# 51.net
KiCad netlist of a schematic drawn in Altium Designer
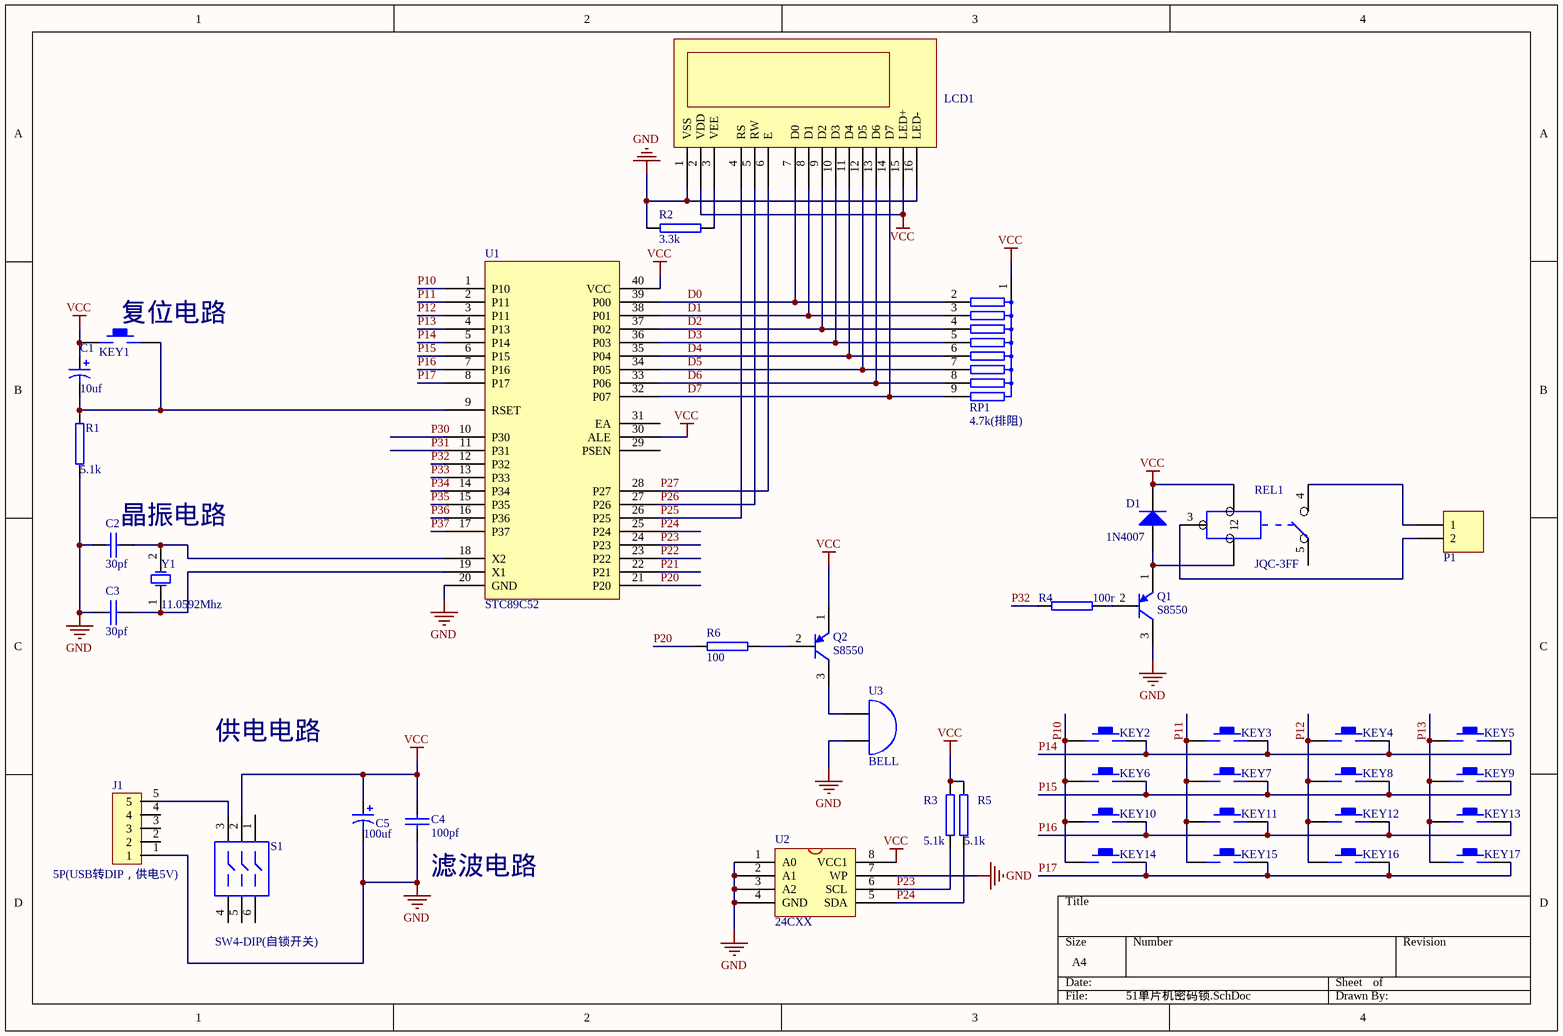
[diagram p0: 51单片机密码锁.SchDoc]

(export (version "E")
  (design (tool "Eeschema 10.0.6"))
  (components
    (comp (ref "C1")
      (value "10uf")
      (footprint "RB.2/.4")
      (description "Polarized Capacitor (Axial)")
      (fields (field (name "VAULE") "10uf") (field (name "PUBLISHER") "Altium Limited"))
      (libsource (lib "my") (part "CAPPOL"))
    )
    (comp (ref "C2") (value "30pf") (footprint "C0.2") (libsource (lib "my") (part "CAP")))
    (comp (ref "C3") (value "30pf") (footprint "C0.2") (libsource (lib "my") (part "CAP")))
    (comp (ref "C4") (value "100pf") (footprint "C0.2") (libsource (lib "my") (part "CAP")))
    (comp (ref "C5")
      (value "100uf")
      (footprint "RB.2/.4")
      (description "Polarized Capacitor (Axial)")
      (fields (field (name "PUBLISHER") "Altium Limited"))
      (libsource (lib "my") (part "CAPPOL"))
    )
    (comp (ref "D1")
      (value "Diode")
      (footprint "DIODE-0.4")
      (description "二极管")
      (fields (field (name "TYPE") "1N4007") (field (name "PUBLISHER") "Altium Limited"))
      (libsource (lib "my封装") (part "Diode"))
    )
    (comp (ref "J1") (value "5P(USB转DIP，供电5V)") (footprint "5P") (libsource (lib "my封装") (part "5P")))
    (comp (ref "KEY1") (value "KEY") (footprint "KEY") (libsource (lib "my电子集成封装库") (part "KEY")))
    (comp (ref "KEY2")
      (value "KEY")
      (footprint "KEY")
      (description "按键")
      (libsource (lib "my封装") (part "KEY"))
    )
    (comp (ref "KEY3")
      (value "KEY")
      (footprint "KEY")
      (description "按键")
      (libsource (lib "my封装") (part "KEY"))
    )
    (comp (ref "KEY4")
      (value "KEY")
      (footprint "KEY")
      (description "按键")
      (libsource (lib "my封装") (part "KEY"))
    )
    (comp (ref "KEY5")
      (value "KEY")
      (footprint "KEY")
      (description "按键")
      (libsource (lib "my封装") (part "KEY"))
    )
    (comp (ref "KEY6")
      (value "KEY")
      (footprint "KEY")
      (description "按键")
      (libsource (lib "my封装") (part "KEY"))
    )
    (comp (ref "KEY7")
      (value "KEY")
      (footprint "KEY")
      (description "按键")
      (libsource (lib "my封装") (part "KEY"))
    )
    (comp (ref "KEY8")
      (value "KEY")
      (footprint "KEY")
      (description "按键")
      (libsource (lib "my封装") (part "KEY"))
    )
    (comp (ref "KEY9")
      (value "KEY")
      (footprint "KEY")
      (description "按键")
      (libsource (lib "my封装") (part "KEY"))
    )
    (comp (ref "KEY10")
      (value "KEY")
      (footprint "KEY")
      (description "按键")
      (libsource (lib "my封装") (part "KEY"))
    )
    (comp (ref "KEY11")
      (value "KEY")
      (footprint "KEY")
      (description "按键")
      (libsource (lib "my封装") (part "KEY"))
    )
    (comp (ref "KEY12")
      (value "KEY")
      (footprint "KEY")
      (description "按键")
      (libsource (lib "my封装") (part "KEY"))
    )
    (comp (ref "KEY13")
      (value "KEY")
      (footprint "KEY")
      (description "按键")
      (libsource (lib "my封装") (part "KEY"))
    )
    (comp (ref "KEY14")
      (value "KEY")
      (footprint "KEY")
      (description "按键")
      (libsource (lib "my封装") (part "KEY"))
    )
    (comp (ref "KEY15")
      (value "KEY")
      (footprint "KEY")
      (description "按键")
      (libsource (lib "my封装") (part "KEY"))
    )
    (comp (ref "KEY16")
      (value "KEY")
      (footprint "KEY")
      (description "按键")
      (libsource (lib "my封装") (part "KEY"))
    )
    (comp (ref "KEY17")
      (value "KEY")
      (footprint "KEY")
      (description "按键")
      (libsource (lib "my封装") (part "KEY"))
    )
    (comp (ref "LCD1") (value "LCD1602") (footprint "SIP16") (libsource (lib "my封装") (part "LCD1602")))
    (comp (ref "P1")
      (value "Header 2")
      (footprint "HDR2X1_A")
      (description "接插件")
      (fields (field (name "PUBLISHER") "Altium Limited"))
      (libsource (lib "my封装") (part "Header 2"))
    )
    (comp (ref "Q1")
      (value "S8550")
      (footprint "TO-92A")
      (description "PNP三极管")
      (fields (field (name "PUBLISHER") "Altium Limited"))
      (libsource (lib "my封装") (part "S8550"))
    )
    (comp (ref "Q2")
      (value "S8550")
      (footprint "TO-92A")
      (description "PNP三极管")
      (fields (field (name "PUBLISHER") "Altium Limited"))
      (libsource (lib "my封装") (part "S8550"))
    )
    (comp (ref "R1") (value "5.1k") (footprint "AXIAL0.4") (libsource (lib "my") (part "RES")))
    (comp (ref "R2")
      (value "3.3k")
      (footprint "AXIAL0.4")
      (description "电阻")
      (libsource (lib "my封装") (part "RES"))
    )
    (comp (ref "R3") (value "5.1k") (footprint "AXIAL0.4") (libsource (lib "my") (part "RES")))
    (comp (ref "R4") (value "100r") (footprint "AXIAL0.4") (libsource (lib "my") (part "RES")))
    (comp (ref "R5") (value "5.1k") (footprint "AXIAL0.4") (libsource (lib "my") (part "RES")))
    (comp (ref "R6")
      (value "100")
      (footprint "AXIAL0.4")
      (description "电阻")
      (libsource (lib "my封装") (part "RES"))
    )
    (comp (ref "REL1")
      (value "JQC-3FF")
      (footprint "JQC-3FF-1")
      (description "继电器")
      (libsource (lib "my封装") (part "REL-5"))
    )
    (comp (ref "RP1") (value "4.7k(排阻)") (footprint "SIP9") (libsource (lib "my电子集成封装库") (part "RP8")))
    (comp (ref "S1") (value "SW4-DIP(自锁开关)") (footprint "SW6") (libsource (lib "my封装") (part "SW4-DIP")))
    (comp (ref "U1") (value "STC89C52") (footprint "DIP40") (libsource (lib "my") (part "STC89C52")))
    (comp (ref "U2")
      (value "24CXX")
      (footprint "DIP8")
      (description "存储芯片")
      (libsource (lib "my封装") (part "24CXX"))
    )
    (comp (ref "U3")
      (value "BELL")
      (footprint "BELL")
      (description "蜂鸣器")
      (libsource (lib "my封装") (part "BELL"))
    )
    (comp (ref "Y1")
      (value "11.0592Mhz")
      (footprint "CRYSTAL")
      (description "Crystal Oscillator")
      (fields (field (name "PUBLISHER") "*"))
      (libsource (lib "CRYSTALS") (part "XTAL"))
    )
  )
  (nets
    (net (code "1") (name "/D0") (class "Default")
      (node (ref "LCD1") (pin "7") (pinfunction "D0_7") (pintype "passive"))
      (node (ref "RP1") (pin "2") (pintype "passive"))
      (node (ref "U1") (pin "39") (pinfunction "P00_39") (pintype "passive"))
    )
    (net (code "2") (name "/D1") (class "Default")
      (node (ref "LCD1") (pin "8") (pinfunction "D1_8") (pintype "passive"))
      (node (ref "RP1") (pin "3") (pintype "passive"))
      (node (ref "U1") (pin "38") (pinfunction "P01_38") (pintype "passive"))
    )
    (net (code "3") (name "/D2") (class "Default")
      (node (ref "LCD1") (pin "9") (pinfunction "D2_9") (pintype "passive"))
      (node (ref "RP1") (pin "4") (pintype "passive"))
      (node (ref "U1") (pin "37") (pinfunction "P02_37") (pintype "passive"))
    )
    (net (code "4") (name "/D3") (class "Default")
      (node (ref "LCD1") (pin "10") (pinfunction "D3_10") (pintype "passive"))
      (node (ref "RP1") (pin "5") (pintype "passive"))
      (node (ref "U1") (pin "36") (pinfunction "P03_36") (pintype "passive"))
    )
    (net (code "5") (name "/D4") (class "Default")
      (node (ref "LCD1") (pin "11") (pinfunction "D4_11") (pintype "passive"))
      (node (ref "RP1") (pin "6") (pintype "passive"))
      (node (ref "U1") (pin "35") (pinfunction "P04_35") (pintype "passive"))
    )
    (net (code "6") (name "/D5") (class "Default")
      (node (ref "LCD1") (pin "12") (pinfunction "D5_12") (pintype "passive"))
      (node (ref "RP1") (pin "7") (pintype "passive"))
      (node (ref "U1") (pin "34") (pinfunction "P05_34") (pintype "passive"))
    )
    (net (code "7") (name "/D6") (class "Default")
      (node (ref "LCD1") (pin "13") (pinfunction "D6_13") (pintype "passive"))
      (node (ref "RP1") (pin "8") (pintype "passive"))
      (node (ref "U1") (pin "33") (pinfunction "P06_33") (pintype "passive"))
    )
    (net (code "8") (name "/D7") (class "Default")
      (node (ref "LCD1") (pin "14") (pinfunction "D7_14") (pintype "passive"))
      (node (ref "RP1") (pin "9") (pintype "passive"))
      (node (ref "U1") (pin "32") (pinfunction "P07_32") (pintype "passive"))
    )
    (net (code "9") (name "/P10") (class "Default")
      (node (ref "KEY10") (pin "1") (pinfunction "1_1") (pintype "passive"))
      (node (ref "KEY14") (pin "1") (pinfunction "1_1") (pintype "passive"))
      (node (ref "KEY2") (pin "1") (pinfunction "1_1") (pintype "passive"))
      (node (ref "KEY6") (pin "1") (pinfunction "1_1") (pintype "passive"))
      (node (ref "U1") (pin "1") (pinfunction "P10_1") (pintype "passive"))
    )
    (net (code "10") (name "/P11") (class "Default")
      (node (ref "KEY11") (pin "1") (pinfunction "1_1") (pintype "passive"))
      (node (ref "KEY15") (pin "1") (pinfunction "1_1") (pintype "passive"))
      (node (ref "KEY3") (pin "1") (pinfunction "1_1") (pintype "passive"))
      (node (ref "KEY7") (pin "1") (pinfunction "1_1") (pintype "passive"))
      (node (ref "U1") (pin "2") (pinfunction "P11_2") (pintype "passive"))
    )
    (net (code "11") (name "/P12") (class "Default")
      (node (ref "KEY12") (pin "1") (pinfunction "1_1") (pintype "passive"))
      (node (ref "KEY16") (pin "1") (pinfunction "1_1") (pintype "passive"))
      (node (ref "KEY4") (pin "1") (pinfunction "1_1") (pintype "passive"))
      (node (ref "KEY8") (pin "1") (pinfunction "1_1") (pintype "passive"))
      (node (ref "U1") (pin "3") (pinfunction "P11_3") (pintype "passive"))
    )
    (net (code "12") (name "/P13") (class "Default")
      (node (ref "KEY13") (pin "1") (pinfunction "1_1") (pintype "passive"))
      (node (ref "KEY17") (pin "1") (pinfunction "1_1") (pintype "passive"))
      (node (ref "KEY5") (pin "1") (pinfunction "1_1") (pintype "passive"))
      (node (ref "KEY9") (pin "1") (pinfunction "1_1") (pintype "passive"))
      (node (ref "U1") (pin "4") (pinfunction "P13_4") (pintype "passive"))
    )
    (net (code "13") (name "/P14") (class "Default")
      (node (ref "KEY2") (pin "2") (pinfunction "2_2") (pintype "passive"))
      (node (ref "KEY3") (pin "2") (pinfunction "2_2") (pintype "passive"))
      (node (ref "KEY4") (pin "2") (pinfunction "2_2") (pintype "passive"))
      (node (ref "KEY5") (pin "2") (pinfunction "2_2") (pintype "passive"))
      (node (ref "U1") (pin "5") (pinfunction "P14_5") (pintype "passive"))
    )
    (net (code "14") (name "/P15") (class "Default")
      (node (ref "KEY6") (pin "2") (pinfunction "2_2") (pintype "passive"))
      (node (ref "KEY7") (pin "2") (pinfunction "2_2") (pintype "passive"))
      (node (ref "KEY8") (pin "2") (pinfunction "2_2") (pintype "passive"))
      (node (ref "KEY9") (pin "2") (pinfunction "2_2") (pintype "passive"))
      (node (ref "U1") (pin "6") (pinfunction "P15_6") (pintype "passive"))
    )
    (net (code "15") (name "/P16") (class "Default")
      (node (ref "KEY10") (pin "2") (pinfunction "2_2") (pintype "passive"))
      (node (ref "KEY11") (pin "2") (pinfunction "2_2") (pintype "passive"))
      (node (ref "KEY12") (pin "2") (pinfunction "2_2") (pintype "passive"))
      (node (ref "KEY13") (pin "2") (pinfunction "2_2") (pintype "passive"))
      (node (ref "U1") (pin "7") (pinfunction "P16_7") (pintype "passive"))
    )
    (net (code "16") (name "/P17") (class "Default")
      (node (ref "KEY14") (pin "2") (pinfunction "2_2") (pintype "passive"))
      (node (ref "KEY15") (pin "2") (pinfunction "2_2") (pintype "passive"))
      (node (ref "KEY16") (pin "2") (pinfunction "2_2") (pintype "passive"))
      (node (ref "KEY17") (pin "2") (pinfunction "2_2") (pintype "passive"))
      (node (ref "U1") (pin "8") (pinfunction "P17_8") (pintype "passive"))
    )
    (net (code "17") (name "/P20") (class "Default")
      (node (ref "R6") (pin "1") (pinfunction "1_1") (pintype "passive"))
      (node (ref "U1") (pin "21") (pinfunction "P20_21") (pintype "passive"))
    )
    (net (code "18") (name "/P21") (class "Default")
      (node (ref "U1") (pin "22") (pinfunction "P21_22") (pintype "passive"))
    )
    (net (code "19") (name "/P22") (class "Default")
      (node (ref "U1") (pin "23") (pinfunction "P22_23") (pintype "passive"))
    )
    (net (code "20") (name "/P23") (class "Default")
      (node (ref "R3") (pin "1") (pinfunction "1_1") (pintype "passive"))
      (node (ref "U1") (pin "24") (pinfunction "P23_24") (pintype "passive"))
      (node (ref "U2") (pin "6") (pinfunction "SCL_6") (pintype "passive"))
    )
    (net (code "21") (name "/P24") (class "Default")
      (node (ref "R5") (pin "1") (pinfunction "1_1") (pintype "passive"))
      (node (ref "U1") (pin "25") (pinfunction "P24_25") (pintype "passive"))
      (node (ref "U2") (pin "5") (pinfunction "SDA_5") (pintype "passive"))
    )
    (net (code "22") (name "/P25") (class "Default")
      (node (ref "LCD1") (pin "4") (pinfunction "RS_4") (pintype "passive"))
      (node (ref "U1") (pin "26") (pinfunction "P25_26") (pintype "passive"))
    )
    (net (code "23") (name "/P26") (class "Default")
      (node (ref "LCD1") (pin "5") (pinfunction "RW_5") (pintype "passive"))
      (node (ref "U1") (pin "27") (pinfunction "P26_27") (pintype "passive"))
    )
    (net (code "24") (name "/P27") (class "Default")
      (node (ref "LCD1") (pin "6") (pinfunction "E_6") (pintype "passive"))
      (node (ref "U1") (pin "28") (pinfunction "P27_28") (pintype "passive"))
    )
    (net (code "25") (name "/P30") (class "Default")
      (node (ref "U1") (pin "10") (pinfunction "P30_10") (pintype "passive"))
    )
    (net (code "26") (name "/P31") (class "Default")
      (node (ref "U1") (pin "11") (pinfunction "P31_11") (pintype "passive"))
    )
    (net (code "27") (name "/P32") (class "Default")
      (node (ref "R4") (pin "1") (pinfunction "1_1") (pintype "passive"))
      (node (ref "U1") (pin "12") (pinfunction "P32_12") (pintype "passive"))
    )
    (net (code "28") (name "/P33") (class "Default")
      (node (ref "U1") (pin "13") (pinfunction "P33_13") (pintype "passive"))
    )
    (net (code "29") (name "/P34") (class "Default")
      (node (ref "U1") (pin "14") (pinfunction "P34_14") (pintype "passive"))
    )
    (net (code "30") (name "/P35") (class "Default")
      (node (ref "U1") (pin "15") (pinfunction "P35_15") (pintype "passive"))
    )
    (net (code "31") (name "/P36") (class "Default")
      (node (ref "U1") (pin "16") (pinfunction "P36_16") (pintype "passive"))
    )
    (net (code "32") (name "/P37") (class "Default")
      (node (ref "U1") (pin "17") (pinfunction "P37_17") (pintype "passive"))
    )
    (net (code "33") (name "GND") (class "Default")
      (node (ref "C2") (pin "1") (pinfunction "1_1") (pintype "passive"))
      (node (ref "C3") (pin "1") (pinfunction "1_1") (pintype "passive"))
      (node (ref "C4") (pin "1") (pinfunction "1_1") (pintype "passive"))
      (node (ref "C5") (pin "2") (pinfunction "2_2") (pintype "passive"))
      (node (ref "J1") (pin "1") (pinfunction "1_1") (pintype "passive"))
      (node (ref "LCD1") (pin "1") (pinfunction "VSS_1") (pintype "passive"))
      (node (ref "LCD1") (pin "16") (pinfunction "LED-_16") (pintype "passive"))
      (node (ref "Q1") (pin "3") (pinfunction "C_3") (pintype "passive"))
      (node (ref "R1") (pin "1") (pinfunction "1_1") (pintype "passive"))
      (node (ref "R2") (pin "1") (pinfunction "1_1") (pintype "passive"))
      (node (ref "U1") (pin "20") (pinfunction "GND_20") (pintype "passive"))
      (node (ref "U2") (pin "1") (pinfunction "A0_1") (pintype "passive"))
      (node (ref "U2") (pin "2") (pinfunction "A1_2") (pintype "passive"))
      (node (ref "U2") (pin "3") (pinfunction "A2_3") (pintype "passive"))
      (node (ref "U2") (pin "4") (pinfunction "GND_4") (pintype "passive"))
      (node (ref "U2") (pin "7") (pinfunction "WP_7") (pintype "passive"))
      (node (ref "U3") (pin "2") (pinfunction "B_2") (pintype "passive"))
    )
    (net (code "34") (name "Net-(D1-A)") (class "Default")
      (node (ref "D1") (pin "1") (pinfunction "A_1") (pintype "passive"))
      (node (ref "Q1") (pin "1") (pinfunction "E_1") (pintype "passive"))
      (node (ref "REL1") (pin "1") (pinfunction "1_1") (pintype "passive"))
    )
    (net (code "35") (name "Net-(J1-Pad5)") (class "Default")
      (node (ref "J1") (pin "5") (pinfunction "5_5") (pintype "passive"))
      (node (ref "S1") (pin "3") (pinfunction "3_3") (pintype "passive"))
    )
    (net (code "36") (name "Net-(LCD1-VEE)") (class "Default")
      (node (ref "LCD1") (pin "3") (pinfunction "VEE_3") (pintype "passive"))
      (node (ref "R2") (pin "2") (pinfunction "2_2") (pintype "passive"))
    )
    (net (code "37") (name "Net-(P1-Pad1)") (class "Default")
      (node (ref "P1") (pin "1") (pinfunction "1_1") (pintype "passive"))
      (node (ref "REL1") (pin "4") (pinfunction "4_4") (pintype "passive"))
    )
    (net (code "38") (name "Net-(P1-Pad2)") (class "Default")
      (node (ref "P1") (pin "2") (pinfunction "2_2") (pintype "passive"))
      (node (ref "REL1") (pin "3") (pinfunction "3_3") (pintype "passive"))
    )
    (net (code "39") (name "Net-(Q1-B)") (class "Default")
      (node (ref "Q1") (pin "2") (pinfunction "B_2") (pintype "passive"))
      (node (ref "R4") (pin "2") (pinfunction "2_2") (pintype "passive"))
    )
    (net (code "40") (name "Net-(Q2-B)") (class "Default")
      (node (ref "Q2") (pin "2") (pinfunction "B_2") (pintype "passive"))
      (node (ref "R6") (pin "2") (pinfunction "2_2") (pintype "passive"))
    )
    (net (code "41") (name "Net-(Q2-C)") (class "Default")
      (node (ref "Q2") (pin "3") (pinfunction "C_3") (pintype "passive"))
      (node (ref "U3") (pin "1") (pinfunction "A_1") (pintype "passive"))
    )
    (net (code "42") (name "Net-(U1-RSET)") (class "Default")
      (node (ref "C1") (pin "2") (pinfunction "2_2") (pintype "passive"))
      (node (ref "KEY1") (pin "2") (pinfunction "2_2") (pintype "passive"))
      (node (ref "R1") (pin "2") (pinfunction "2_2") (pintype "passive"))
      (node (ref "U1") (pin "9") (pinfunction "RSET_9") (pintype "passive"))
    )
    (net (code "43") (name "Net-(U1-X1)") (class "Default")
      (node (ref "C3") (pin "2") (pinfunction "2_2") (pintype "passive"))
      (node (ref "U1") (pin "19") (pinfunction "X1_19") (pintype "passive"))
      (node (ref "Y1") (pin "1") (pinfunction "OSC1_1") (pintype "passive"))
    )
    (net (code "44") (name "Net-(U1-X2)") (class "Default")
      (node (ref "C2") (pin "2") (pinfunction "2_2") (pintype "passive"))
      (node (ref "U1") (pin "18") (pinfunction "X2_18") (pintype "passive"))
      (node (ref "Y1") (pin "2") (pinfunction "OSC2_2") (pintype "passive"))
    )
    (net (code "45") (name "VCC") (class "Default")
      (node (ref "C1") (pin "1") (pinfunction "1_1") (pintype "passive"))
      (node (ref "C4") (pin "2") (pinfunction "2_2") (pintype "passive"))
      (node (ref "C5") (pin "1") (pinfunction "1_1") (pintype "passive"))
      (node (ref "D1") (pin "2") (pinfunction "K_2") (pintype "passive"))
      (node (ref "KEY1") (pin "1") (pinfunction "1_1") (pintype "passive"))
      (node (ref "LCD1") (pin "15") (pinfunction "LED+_15") (pintype "passive"))
      (node (ref "LCD1") (pin "2") (pinfunction "VDD_2") (pintype "passive"))
      (node (ref "Q2") (pin "1") (pinfunction "E_1") (pintype "passive"))
      (node (ref "R3") (pin "2") (pinfunction "2_2") (pintype "passive"))
      (node (ref "R5") (pin "2") (pinfunction "2_2") (pintype "passive"))
      (node (ref "REL1") (pin "2") (pinfunction "2_2") (pintype "passive"))
      (node (ref "RP1") (pin "1") (pintype "passive"))
      (node (ref "S1") (pin "2") (pinfunction "2_2") (pintype "passive"))
      (node (ref "U1") (pin "30") (pinfunction "ALE_30") (pintype "passive"))
      (node (ref "U1") (pin "40") (pinfunction "VCC_40") (pintype "passive"))
      (node (ref "U2") (pin "8") (pinfunction "VCC1_8") (pintype "passive"))
    )
    (net (code "46") (name "unconnected-(J1-Pad2)") (class "Default")
      (node (ref "J1") (pin "2") (pinfunction "2_2") (pintype "passive"))
    )
    (net (code "47") (name "unconnected-(J1-Pad3)") (class "Default")
      (node (ref "J1") (pin "3") (pinfunction "3_3") (pintype "passive"))
    )
    (net (code "48") (name "unconnected-(J1-Pad4)") (class "Default")
      (node (ref "J1") (pin "4") (pinfunction "4_4") (pintype "passive"))
    )
    (net (code "49") (name "unconnected-(REL1-Pad5)") (class "Default")
      (node (ref "REL1") (pin "5") (pinfunction "5_5") (pintype "passive"))
    )
    (net (code "50") (name "unconnected-(S1-Pad1)") (class "Default")
      (node (ref "S1") (pin "1") (pinfunction "1_1") (pintype "passive"))
    )
    (net (code "51") (name "unconnected-(S1-Pad4)") (class "Default")
      (node (ref "S1") (pin "4") (pinfunction "4_4") (pintype "passive"))
    )
    (net (code "52") (name "unconnected-(S1-Pad5)") (class "Default")
      (node (ref "S1") (pin "5") (pinfunction "5_5") (pintype "passive"))
    )
    (net (code "53") (name "unconnected-(S1-Pad6)") (class "Default")
      (node (ref "S1") (pin "6") (pinfunction "6_6") (pintype "passive"))
    )
    (net (code "54") (name "unconnected-(U1-EA-Pad31)") (class "Default")
      (node (ref "U1") (pin "31") (pinfunction "EA_31") (pintype "passive"))
    )
    (net (code "55") (name "unconnected-(U1-PSEN-Pad29)") (class "Default")
      (node (ref "U1") (pin "29") (pinfunction "PSEN_29") (pintype "passive"))
    )
  )
)
